# PBM_soldeerbout.net
KiCad netlist of a schematic drawn in Altium Designer
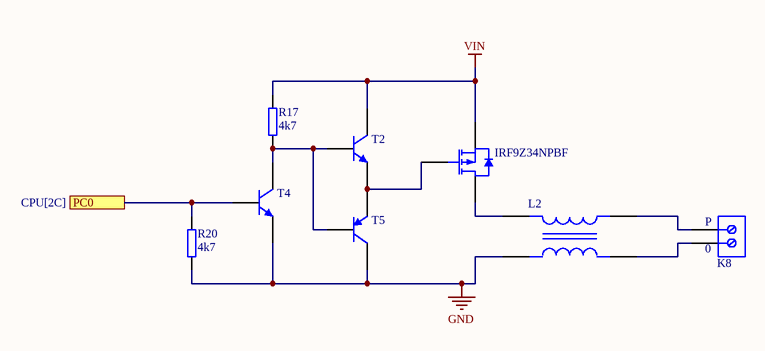
[diagram p0: PBM_soldeerbout.SchDoc]

(export (version "E")
  (design (tool "Eeschema 10.0.6"))
  (components
    (comp (ref "IRF9Z34NPBF")
      (value "MOSFET_P")
      (footprint "TO_252")
      (fields (field (name "MANUFACTURER") "Fairchild Semiconductor"))
      (libsource (lib "Soldeerstation_Final (1)") (part "MOSFET_P"))
    )
    (comp (ref "K8")
      (value "282836-2")
      (footprint "terminal_block")
      (description "Female Header, Pitch 5 mm, 1 x 2 Position, Height 10 mm, Tail Length 3.5 mm, Rohs, Bulk")
      (fields (field (name "VOLTAGE") "300V") (field (name "MANUFACTURER") "TE Connectivity"))
      (libsource (lib "Schlib1") (part "1x2 terminal block"))
    )
    (comp (ref "L2")
      (value "Common_Mode_Choke")
      (footprint "2545")
      (libsource (lib "Soldeerstation_Final (1)") (part "Common_Mode_Choke"))
    )
    (comp (ref "R17")
      (value "4k7")
      (footprint "CC_0805_m")
      (fields (field (name "MANUFACTURER") "Vishay Dale") (field (name "PART NUMBER") "CRCW08050000Z0EA"))
      (libsource (lib "Soldeerstation_Final (1)") (part "Resistor"))
    )
    (comp (ref "R20")
      (value "4k7")
      (footprint "R_0805_L")
      (fields (field (name "MANUFACTURER") "Vishay Dale") (field (name "PART NUMBER") "CRCW08050000Z0EA"))
      (libsource (lib "Soldeerstation_Final (1)") (part "Resistor"))
    )
    (comp (ref "T2")
      (value "BC547")
      (footprint "SOT_23")
      (fields (field (name "MANUFACTURER") "On Semiconductor") (field (name "PARTNUMBER") "BC547C"))
      (libsource (lib "Soldeerstation_Final (1)") (part "Transistor_NPN"))
    )
    (comp (ref "T4")
      (value "BC547")
      (footprint "SOT_23")
      (fields (field (name "MANUFACTURER") "On Semiconductor") (field (name "PARTNUMBER") "BC547C"))
      (libsource (lib "Soldeerstation_Final (1)") (part "Transistor_NPN"))
    )
    (comp (ref "T5")
      (value "BC557")
      (footprint "SOT_23")
      (fields (field (name "MANUFACTURER") "On Semiconductor") (field (name "PARTNUMBER") "BC557C"))
      (libsource (lib "Soldeerstation_Final (1)") (part "Transistor_PNP"))
    )
  )
  (nets
    (net (code "1") (name "/PC0") (class "Default")
      (node (ref "R20") (pin "2") (pinfunction "2_2") (pintype "passive"))
      (node (ref "T4") (pin "2") (pinfunction "B_2") (pintype "passive"))
    )
    (net (code "2") (name "GND") (class "Default")
      (node (ref "L2") (pin "2") (pinfunction "2_2") (pintype "passive"))
      (node (ref "R20") (pin "1") (pinfunction "1_1") (pintype "passive"))
      (node (ref "T4") (pin "3") (pinfunction "E_3") (pintype "passive"))
      (node (ref "T5") (pin "1") (pinfunction "C_1") (pintype "passive"))
    )
    (net (code "3") (name "Net-(IRF9Z34NPBF-DRAIN)") (class "Default")
      (node (ref "IRF9Z34NPBF") (pin "3") (pinfunction "DRAIN_3") (pintype "passive"))
      (node (ref "L2") (pin "1") (pinfunction "1_1") (pintype "passive"))
    )
    (net (code "4") (name "Net-(IRF9Z34NPBF-GATE)") (class "Default")
      (node (ref "IRF9Z34NPBF") (pin "1") (pinfunction "GATE_1") (pintype "passive"))
      (node (ref "T2") (pin "3") (pinfunction "E_3") (pintype "passive"))
      (node (ref "T5") (pin "3") (pinfunction "E_3") (pintype "passive"))
    )
    (net (code "5") (name "Net-(K8-Pad1)") (class "Default")
      (node (ref "K8") (pin "1") (pinfunction "1_1") (pintype "passive"))
      (node (ref "L2") (pin "4") (pinfunction "4_4") (pintype "passive"))
    )
    (net (code "6") (name "Net-(K8-Pad2)") (class "Default")
      (node (ref "K8") (pin "2") (pinfunction "2_2") (pintype "passive"))
      (node (ref "L2") (pin "3") (pinfunction "3_3") (pintype "passive"))
    )
    (net (code "7") (name "Net-(T2-B)") (class "Default")
      (node (ref "R17") (pin "1") (pinfunction "1_1") (pintype "passive"))
      (node (ref "T2") (pin "2") (pinfunction "B_2") (pintype "passive"))
      (node (ref "T4") (pin "1") (pinfunction "C_1") (pintype "passive"))
      (node (ref "T5") (pin "2") (pinfunction "B_2") (pintype "passive"))
    )
    (net (code "8") (name "VIN") (class "Default")
      (node (ref "IRF9Z34NPBF") (pin "2") (pinfunction "SOURCE_2") (pintype "passive"))
      (node (ref "R17") (pin "2") (pinfunction "2_2") (pintype "passive"))
      (node (ref "T2") (pin "1") (pinfunction "C_1") (pintype "passive"))
    )
  )
)
